# AD.net
KiCad netlist of a schematic drawn in Altium Designer
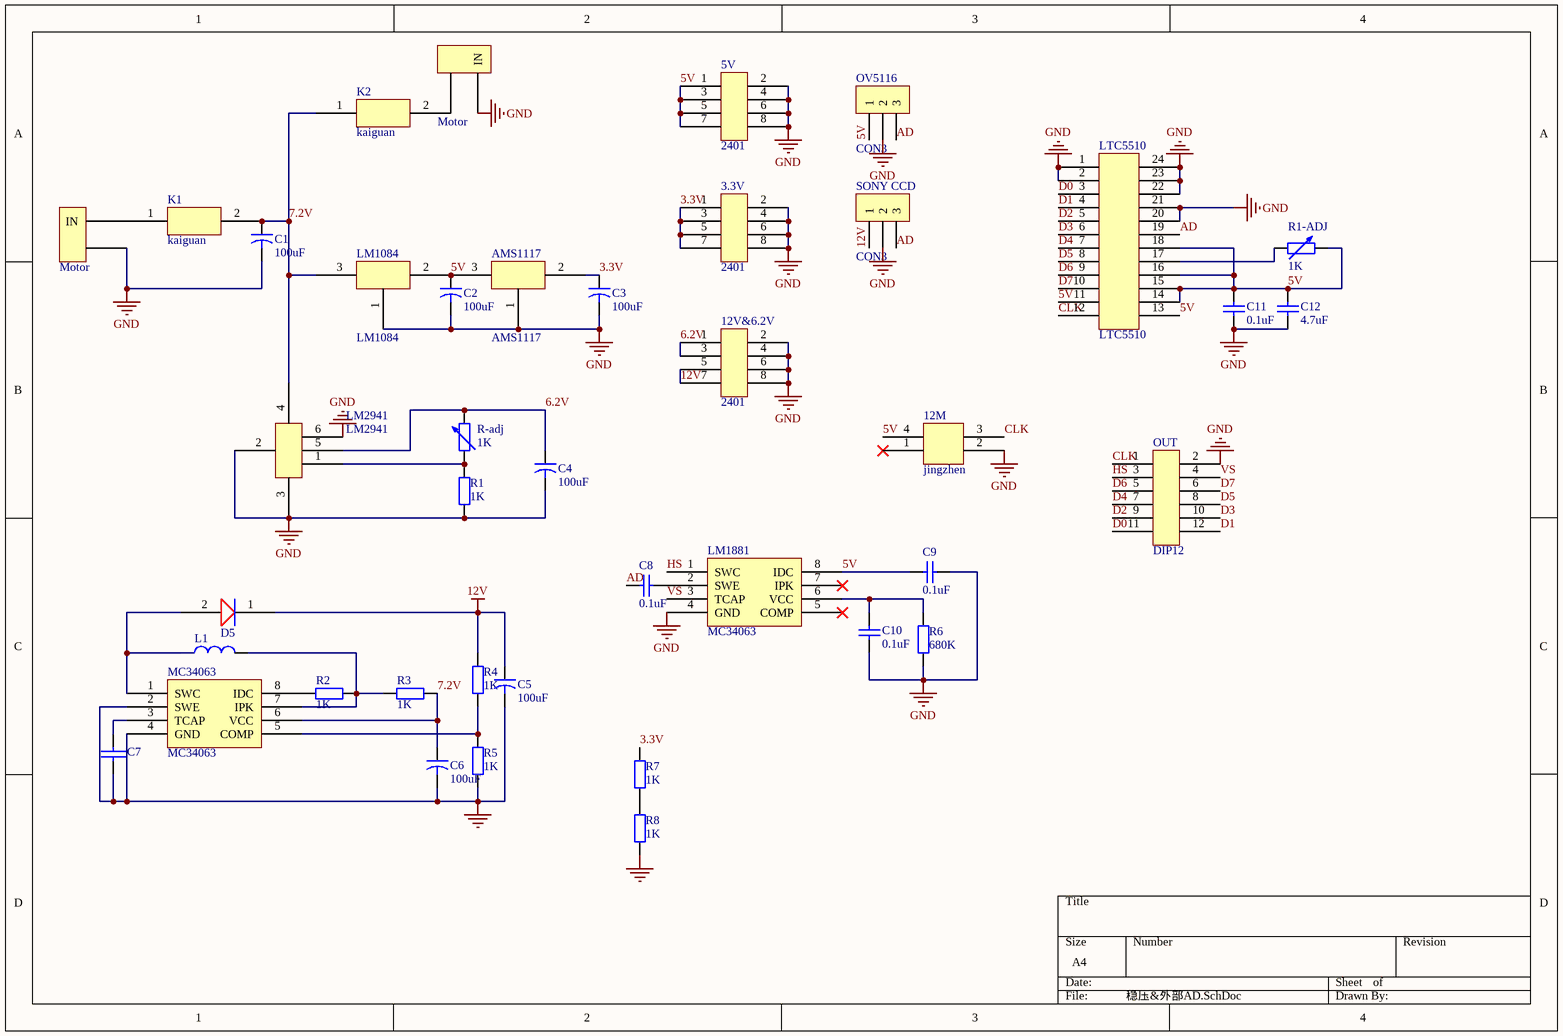
[diagram p0: 稳压&外部AD.SchDoc]

(export (version "E")
  (design (tool "Eeschema 10.0.6"))
  (components
    (comp (ref "3.3V") (value "2401") (footprint "IDC-8") (libsource (lib "Schlib1") (part "2401")))
    (comp (ref "5V") (value "2401") (footprint "IDC-8") (libsource (lib "Schlib1") (part "2401")))
    (comp (ref "12M") (value "jingzhen") (footprint "3225") (libsource (lib "主板常用元器件") (part "jingzhen")))
    (comp (ref "12V&6.2V") (value "2401") (footprint "IDC-8") (libsource (lib "Schlib1") (part "2401")))
    (comp (ref "AMS1117") (value "AMS1117") (footprint "SOT223") (libsource (lib "主板常用元器件") (part "AMS1117")))
    (comp (ref "C1")
      (value "100uF")
      (footprint "CAPPR2-5x6.8")
      (description "Capacitor")
      (fields (field (name "Comment") "Cap2") (field (name "PUBLISHER") "Altium Limited"))
      (libsource (lib "主板常用元器件") (part "Cap2"))
    )
    (comp (ref "C2")
      (value "100uF")
      (footprint "CAPPR2-5x6.8")
      (description "Capacitor")
      (fields (field (name "Comment") "Cap2") (field (name "PUBLISHER") "Altium Limited"))
      (libsource (lib "主板常用元器件") (part "Cap2"))
    )
    (comp (ref "C3")
      (value "100uF")
      (footprint "CAPPR2-5x6.8")
      (description "Capacitor")
      (fields (field (name "Comment") "Cap2") (field (name "PUBLISHER") "Altium Limited"))
      (libsource (lib "主板常用元器件") (part "Cap2"))
    )
    (comp (ref "C4")
      (value "100uF")
      (footprint "CAPPR2-5x6.8")
      (description "Capacitor")
      (fields (field (name "Comment") "Cap2") (field (name "PUBLISHER") "Altium Limited"))
      (libsource (lib "主板常用元器件") (part "Cap2"))
    )
    (comp (ref "C5")
      (value "100uF")
      (footprint "CAPPR2-5x6.8")
      (description "Capacitor")
      (fields (field (name "Comment") "Cap2") (field (name "PUBLISHER") "Altium Limited"))
      (libsource (lib "主板常用元器件") (part "Cap2"))
    )
    (comp (ref "C6")
      (value "100uF")
      (footprint "CAPPR2-5x6.8")
      (description "Capacitor")
      (fields (field (name "Comment") "Cap2") (field (name "PUBLISHER") "Altium Limited"))
      (libsource (lib "主板常用元器件") (part "Cap2"))
    )
    (comp (ref "C7") (value "CAP") (footprint "0805") (libsource (lib "常用元件库") (part "CAP")))
    (comp (ref "C8")
      (value "0.1uF")
      (footprint "0805")
      (description "Capacitor")
      (fields (field (name "Comment") "Cap1") (field (name "PUBLISHER") "Altium Limited"))
      (libsource (lib "主板常用元器件") (part "Cap1"))
    )
    (comp (ref "C9")
      (value "0.1uF")
      (footprint "0805")
      (description "Capacitor")
      (fields (field (name "Comment") "Cap1") (field (name "PUBLISHER") "Altium Limited"))
      (libsource (lib "主板常用元器件") (part "Cap1"))
    )
    (comp (ref "C10")
      (value "0.1uF")
      (footprint "0805")
      (description "Capacitor")
      (fields (field (name "Comment") "Cap1") (field (name "PUBLISHER") "Altium Limited"))
      (libsource (lib "主板常用元器件") (part "Cap1"))
    )
    (comp (ref "C11")
      (value "0.1uF")
      (footprint "0805")
      (description "Capacitor")
      (fields (field (name "Comment") "Cap1") (field (name "PUBLISHER") "Altium Limited"))
      (libsource (lib "主板常用元器件") (part "Cap1"))
    )
    (comp (ref "C12")
      (value "4.7uF")
      (footprint "0805")
      (description "Capacitor")
      (fields (field (name "Comment") "Cap1") (field (name "PUBLISHER") "Altium Limited"))
      (libsource (lib "主板常用元器件") (part "Cap1"))
    )
    (comp (ref "D5") (value "1N5819") (footprint "SMA") (libsource (lib "Schlib1") (part "1N5819")))
    (comp (ref "IN") (value "Motor") (footprint "connection") (libsource (lib "") (part "Motor_1")))
    (comp (ref "K1") (value "kaiguan") (footprint "SIP3") (libsource (lib "主板常用元器件") (part "kaiguan")))
    (comp (ref "K2") (value "kaiguan") (footprint "SIP3") (libsource (lib "主板常用元器件") (part "kaiguan")))
    (comp (ref "L1") (value "L") (footprint "L 5*5mm") (libsource (lib "常用元件库") (part "L")))
    (comp (ref "LM1084") (value "LM1084") (footprint "LM1084") (libsource (lib "主板常用元器件") (part "LM1084")))
    (comp (ref "LM1881") (value "MC34063") (footprint "SO-8") (libsource (lib "Schlib1") (part "MC34063")))
    (comp (ref "LM2941") (value "LM2941") (libsource (lib "主板常用元器件") (part "LM2941")))
    (comp (ref "LTC5510")
      (value "LTC5510")
      (footprint "SOP127P780X200-24N")
      (libsource (lib "主板常用元器件") (part "LTC5510"))
    )
    (comp (ref "MC34063") (value "MC34063") (footprint "SO-8") (libsource (lib "Schlib1") (part "MC34063")))
    (comp (ref "Motor") (value "Motor") (footprint "connection") (libsource (lib "主板常用元器件") (part "Motor")))
    (comp (ref "OUT") (value "DIP12") (footprint "IDC-12") (libsource (lib "主板常用元器件") (part "DIP12")))
    (comp (ref "OV5116") (value "CON3") (footprint "SIP3") (libsource (lib "主板常用元器件") (part "CON3")))
    (comp (ref "R-adj")
      (value "1K")
      (footprint "SIP3")
      (description "Variable Resistor")
      (fields (field (name "Comment") "Res Adj2") (field (name "PUBLISHER") "Altium Limited"))
      (libsource (lib "") (part "Res Adj2_1"))
    )
    (comp (ref "R1")
      (value "1K")
      (footprint "0805")
      (description "Resistor")
      (fields (field (name "Comment") "Res2") (field (name "PUBLISHER") "Altium Limited"))
      (libsource (lib "主板常用元器件") (part "Res2"))
    )
    (comp (ref "R1-ADJ")
      (value "1K")
      (footprint "SIP3")
      (description "Variable Resistor")
      (fields (field (name "Comment") "Res Adj2") (field (name "PUBLISHER") "Altium Limited"))
      (libsource (lib "主板常用元器件") (part "Res Adj2"))
    )
    (comp (ref "R2")
      (value "1K")
      (footprint "0805")
      (description "Resistor")
      (fields (field (name "Comment") "Res2") (field (name "PUBLISHER") "Altium Limited"))
      (libsource (lib "") (part "Res2_1"))
    )
    (comp (ref "R3")
      (value "1K")
      (footprint "0805")
      (description "Resistor")
      (fields (field (name "Comment") "Res2") (field (name "PUBLISHER") "Altium Limited"))
      (libsource (lib "") (part "Res2_1"))
    )
    (comp (ref "R4")
      (value "1K")
      (footprint "0805")
      (description "Resistor")
      (fields (field (name "Comment") "Res2") (field (name "PUBLISHER") "Altium Limited"))
      (libsource (lib "主板常用元器件") (part "Res2"))
    )
    (comp (ref "R5")
      (value "1K")
      (footprint "0805")
      (description "Resistor")
      (fields (field (name "Comment") "Res2") (field (name "PUBLISHER") "Altium Limited"))
      (libsource (lib "主板常用元器件") (part "Res2"))
    )
    (comp (ref "R6")
      (value "680K")
      (footprint "0805")
      (description "Resistor")
      (fields (field (name "Comment") "Res2") (field (name "PUBLISHER") "Altium Limited"))
      (libsource (lib "主板常用元器件") (part "Res2"))
    )
    (comp (ref "R7")
      (value "1K")
      (footprint "0805")
      (description "Resistor")
      (fields (field (name "Comment") "Res2") (field (name "PUBLISHER") "Altium Limited"))
      (libsource (lib "主板常用元器件") (part "Res2"))
    )
    (comp (ref "R8")
      (value "1K")
      (footprint "0805")
      (description "Resistor")
      (fields (field (name "Comment") "Res2") (field (name "PUBLISHER") "Altium Limited"))
      (libsource (lib "主板常用元器件") (part "Res2"))
    )
    (comp (ref "SONY CCD") (value "CON3") (footprint "SIP3") (libsource (lib "主板常用元器件") (part "CON3")))
  )
  (nets
    (net (code "1") (name "/3.3V") (class "Default")
      (node (ref "3.3V") (pin "1") (pinfunction "GND_1") (pintype "passive"))
      (node (ref "3.3V") (pin "3") (pinfunction "CE_3") (pintype "passive"))
      (node (ref "3.3V") (pin "5") (pinfunction "SCK_5") (pintype "passive"))
      (node (ref "3.3V") (pin "7") (pinfunction "MISO_7") (pintype "passive"))
      (node (ref "AMS1117") (pin "2") (pinfunction "OUT_2") (pintype "passive"))
      (node (ref "C3") (pin "1") (pinfunction "1_1") (pintype "passive"))
      (node (ref "R7") (pin "2") (pinfunction "2_2") (pintype "passive"))
    )
    (net (code "2") (name "/5V") (class "Default")
      (node (ref "12M") (pin "4") (pinfunction "VCC_4") (pintype "passive"))
      (node (ref "5V") (pin "1") (pinfunction "GND_1") (pintype "passive"))
      (node (ref "5V") (pin "3") (pinfunction "CE_3") (pintype "passive"))
      (node (ref "5V") (pin "5") (pinfunction "SCK_5") (pintype "passive"))
      (node (ref "5V") (pin "7") (pinfunction "MISO_7") (pintype "passive"))
      (node (ref "AMS1117") (pin "3") (pinfunction "IN_3") (pintype "passive"))
      (node (ref "C11") (pin "2") (pinfunction "2_2") (pintype "passive"))
      (node (ref "C12") (pin "2") (pinfunction "2_2") (pintype "passive"))
      (node (ref "C2") (pin "1") (pinfunction "1_1") (pintype "passive"))
      (node (ref "C9") (pin "1") (pinfunction "1_1") (pintype "passive"))
      (node (ref "LM1084") (pin "2") (pinfunction "OUT_2") (pintype "passive"))
      (node (ref "LM1881") (pin "8") (pinfunction "IDC_8") (pintype "passive"))
      (node (ref "LTC5510") (pin "11") (pinfunction "11_11") (pintype "passive"))
      (node (ref "LTC5510") (pin "13") (pinfunction "13_13") (pintype "passive"))
      (node (ref "LTC5510") (pin "14") (pinfunction "14_14") (pintype "passive"))
      (node (ref "LTC5510") (pin "15") (pinfunction "15_15") (pintype "passive"))
      (node (ref "LTC5510") (pin "16") (pinfunction "16_16") (pintype "passive"))
      (node (ref "LTC5510") (pin "18") (pinfunction "18_18") (pintype "passive"))
      (node (ref "OV5116") (pin "1") (pinfunction "1_1") (pintype "passive"))
      (node (ref "R1-ADJ") (pin "2") (pinfunction "2_2") (pintype "passive"))
    )
    (net (code "3") (name "/6.2V") (class "Default")
      (node (ref "12V&6.2V") (pin "1") (pinfunction "GND_1") (pintype "passive"))
      (node (ref "12V&6.2V") (pin "3") (pinfunction "CE_3") (pintype "passive"))
      (node (ref "C4") (pin "1") (pinfunction "1_1") (pintype "passive"))
      (node (ref "LM2941") (pin "5") (pinfunction "OUT_5") (pintype "passive"))
      (node (ref "R-adj") (pin "2") (pinfunction "2_2") (pintype "passive"))
    )
    (net (code "4") (name "/7.2V") (class "Default")
      (node (ref "C1") (pin "1") (pinfunction "1_1") (pintype "passive"))
      (node (ref "C6") (pin "1") (pinfunction "1_1") (pintype "passive"))
      (node (ref "K1") (pin "2") (pinfunction "IN_2") (pintype "passive"))
      (node (ref "K2") (pin "1") (pinfunction "IN_1") (pintype "passive"))
      (node (ref "LM1084") (pin "3") (pinfunction "IN_3") (pintype "passive"))
      (node (ref "LM2941") (pin "4") (pinfunction "IN_4") (pintype "passive"))
      (node (ref "MC34063") (pin "6") (pinfunction "VCC_6") (pintype "passive"))
      (node (ref "R3") (pin "1") (pinfunction "1_1") (pintype "passive"))
    )
    (net (code "5") (name "/AD") (class "Default")
      (node (ref "C8") (pin "1") (pinfunction "1_1") (pintype "passive"))
      (node (ref "LTC5510") (pin "19") (pinfunction "19_19") (pintype "passive"))
      (node (ref "OV5116") (pin "3") (pinfunction "3_3") (pintype "passive"))
      (node (ref "SONY CCD") (pin "3") (pinfunction "3_3") (pintype "passive"))
    )
    (net (code "6") (name "/CLK") (class "Default")
      (node (ref "12M") (pin "3") (pinfunction "OUT_3") (pintype "passive"))
      (node (ref "LTC5510") (pin "12") (pinfunction "12_12") (pintype "passive"))
      (node (ref "OUT") (pin "1") (pinfunction "1_1") (pintype "passive"))
    )
    (net (code "7") (name "/D0") (class "Default")
      (node (ref "LTC5510") (pin "3") (pinfunction "3_3") (pintype "passive"))
      (node (ref "OUT") (pin "11") (pinfunction "11_11") (pintype "passive"))
    )
    (net (code "8") (name "/D1") (class "Default")
      (node (ref "LTC5510") (pin "4") (pinfunction "4_4") (pintype "passive"))
      (node (ref "OUT") (pin "12") (pinfunction "12_12") (pintype "passive"))
    )
    (net (code "9") (name "/D2") (class "Default")
      (node (ref "LTC5510") (pin "5") (pinfunction "5_5") (pintype "passive"))
      (node (ref "OUT") (pin "9") (pinfunction "9_9") (pintype "passive"))
    )
    (net (code "10") (name "/D3") (class "Default")
      (node (ref "LTC5510") (pin "6") (pinfunction "6_6") (pintype "passive"))
      (node (ref "OUT") (pin "10") (pinfunction "10_10") (pintype "passive"))
    )
    (net (code "11") (name "/D4") (class "Default")
      (node (ref "LTC5510") (pin "7") (pinfunction "7_7") (pintype "passive"))
      (node (ref "OUT") (pin "7") (pinfunction "7_7") (pintype "passive"))
    )
    (net (code "12") (name "/D5") (class "Default")
      (node (ref "LTC5510") (pin "8") (pinfunction "8_8") (pintype "passive"))
      (node (ref "OUT") (pin "8") (pinfunction "8_8") (pintype "passive"))
    )
    (net (code "13") (name "/D6") (class "Default")
      (node (ref "LTC5510") (pin "9") (pinfunction "9_9") (pintype "passive"))
      (node (ref "OUT") (pin "5") (pinfunction "5_5") (pintype "passive"))
    )
    (net (code "14") (name "/D7") (class "Default")
      (node (ref "LTC5510") (pin "10") (pinfunction "10_10") (pintype "passive"))
      (node (ref "OUT") (pin "6") (pinfunction "6_6") (pintype "passive"))
    )
    (net (code "15") (name "/HS") (class "Default")
      (node (ref "LM1881") (pin "1") (pinfunction "SWC_1") (pintype "passive"))
      (node (ref "OUT") (pin "3") (pinfunction "3_3") (pintype "passive"))
    )
    (net (code "16") (name "/VS") (class "Default")
      (node (ref "LM1881") (pin "3") (pinfunction "TCAP_3") (pintype "passive"))
      (node (ref "OUT") (pin "4") (pinfunction "4_4") (pintype "passive"))
    )
    (net (code "17") (name "12V") (class "Default")
      (node (ref "12V&6.2V") (pin "5") (pinfunction "SCK_5") (pintype "passive"))
      (node (ref "12V&6.2V") (pin "7") (pinfunction "MISO_7") (pintype "passive"))
      (node (ref "C5") (pin "1") (pinfunction "1_1") (pintype "passive"))
      (node (ref "D5") (pin "1") (pinfunction "OUT_1") (pintype "passive"))
      (node (ref "R4") (pin "2") (pinfunction "2_2") (pintype "passive"))
      (node (ref "SONY CCD") (pin "1") (pinfunction "1_1") (pintype "passive"))
    )
    (net (code "18") (name "GND") (class "Default")
      (node (ref "12M") (pin "2") (pinfunction "GND_2") (pintype "passive"))
      (node (ref "12V&6.2V") (pin "2") (pinfunction "VCC_2") (pintype "passive"))
      (node (ref "12V&6.2V") (pin "4") (pinfunction "CSN_4") (pintype "passive"))
      (node (ref "12V&6.2V") (pin "6") (pinfunction "MOSI_6") (pintype "passive"))
      (node (ref "12V&6.2V") (pin "8") (pinfunction "IRQ_8") (pintype "passive"))
      (node (ref "3.3V") (pin "2") (pinfunction "VCC_2") (pintype "passive"))
      (node (ref "3.3V") (pin "4") (pinfunction "CSN_4") (pintype "passive"))
      (node (ref "3.3V") (pin "6") (pinfunction "MOSI_6") (pintype "passive"))
      (node (ref "3.3V") (pin "8") (pinfunction "IRQ_8") (pintype "passive"))
      (node (ref "5V") (pin "2") (pinfunction "VCC_2") (pintype "passive"))
      (node (ref "5V") (pin "4") (pinfunction "CSN_4") (pintype "passive"))
      (node (ref "5V") (pin "6") (pinfunction "MOSI_6") (pintype "passive"))
      (node (ref "5V") (pin "8") (pinfunction "IRQ_8") (pintype "passive"))
      (node (ref "AMS1117") (pin "1") (pinfunction "GND_1") (pintype "passive"))
      (node (ref "C1") (pin "2") (pinfunction "2_2") (pintype "passive"))
      (node (ref "C10") (pin "1") (pinfunction "1_1") (pintype "passive"))
      (node (ref "C11") (pin "1") (pinfunction "1_1") (pintype "passive"))
      (node (ref "C12") (pin "1") (pinfunction "1_1") (pintype "passive"))
      (node (ref "C2") (pin "2") (pinfunction "2_2") (pintype "passive"))
      (node (ref "C3") (pin "2") (pinfunction "2_2") (pintype "passive"))
      (node (ref "C4") (pin "2") (pinfunction "2_2") (pintype "passive"))
      (node (ref "C5") (pin "2") (pinfunction "2_2") (pintype "passive"))
      (node (ref "C6") (pin "2") (pinfunction "2_2") (pintype "passive"))
      (node (ref "C7") (pin "2") (pinfunction "2_2") (pintype "passive"))
      (node (ref "C9") (pin "2") (pinfunction "2_2") (pintype "passive"))
      (node (ref "IN") (pin "2") (pinfunction "OUT_2") (pintype "passive"))
      (node (ref "LM1084") (pin "1") (pinfunction "GND_1") (pintype "passive"))
      (node (ref "LM1881") (pin "4") (pinfunction "GND_4") (pintype "passive"))
      (node (ref "LM2941") (pin "2") (pinfunction "OFF_2") (pintype "passive"))
      (node (ref "LM2941") (pin "3") (pinfunction "GND_3") (pintype "passive"))
      (node (ref "LM2941") (pin "6") (pinfunction "OUT_6") (pintype "passive"))
      (node (ref "LTC5510") (pin "1") (pinfunction "1_1") (pintype "passive"))
      (node (ref "LTC5510") (pin "2") (pinfunction "2_2") (pintype "passive"))
      (node (ref "LTC5510") (pin "20") (pinfunction "20_20") (pintype "passive"))
      (node (ref "LTC5510") (pin "21") (pinfunction "21_21") (pintype "passive"))
      (node (ref "LTC5510") (pin "22") (pinfunction "22_22") (pintype "passive"))
      (node (ref "LTC5510") (pin "23") (pinfunction "23_23") (pintype "passive"))
      (node (ref "LTC5510") (pin "24") (pinfunction "24_24") (pintype "passive"))
      (node (ref "MC34063") (pin "2") (pinfunction "SWE_2") (pintype "passive"))
      (node (ref "MC34063") (pin "4") (pinfunction "GND_4") (pintype "passive"))
      (node (ref "Motor") (pin "1") (pinfunction "IN_1") (pintype "passive"))
      (node (ref "OUT") (pin "2") (pinfunction "2_2") (pintype "passive"))
      (node (ref "OV5116") (pin "2") (pinfunction "2_2") (pintype "passive"))
      (node (ref "R1") (pin "1") (pinfunction "1_1") (pintype "passive"))
      (node (ref "R5") (pin "1") (pinfunction "1_1") (pintype "passive"))
      (node (ref "R6") (pin "1") (pinfunction "1_1") (pintype "passive"))
      (node (ref "R8") (pin "1") (pinfunction "1_1") (pintype "passive"))
      (node (ref "SONY CCD") (pin "2") (pinfunction "2_2") (pintype "passive"))
    )
    (net (code "19") (name "Net-(D5-IN)") (class "Default")
      (node (ref "D5") (pin "2") (pinfunction "IN_2") (pintype "passive"))
      (node (ref "L1") (pin "2") (pinfunction "2_2") (pintype "passive"))
      (node (ref "MC34063") (pin "1") (pinfunction "SWC_1") (pintype "passive"))
    )
    (net (code "20") (name "Net-(IN-IN)") (class "Default")
      (node (ref "IN") (pin "1") (pinfunction "IN_1") (pintype "passive"))
      (node (ref "K1") (pin "1") (pinfunction "IN_1") (pintype "passive"))
    )
    (net (code "21") (name "Net-(LM1881-SWE)") (class "Default")
      (node (ref "C8") (pin "2") (pinfunction "2_2") (pintype "passive"))
      (node (ref "LM1881") (pin "2") (pinfunction "SWE_2") (pintype "passive"))
    )
    (net (code "22") (name "Net-(LM1881-VCC)") (class "Default")
      (node (ref "C10") (pin "2") (pinfunction "2_2") (pintype "passive"))
      (node (ref "LM1881") (pin "6") (pinfunction "VCC_6") (pintype "passive"))
      (node (ref "R6") (pin "2") (pinfunction "2_2") (pintype "passive"))
    )
    (net (code "23") (name "Net-(LM2941-ADJ)") (class "Default")
      (node (ref "LM2941") (pin "1") (pinfunction "ADJ_1") (pintype "passive"))
      (node (ref "R-adj") (pin "1") (pinfunction "1_1") (pintype "passive"))
      (node (ref "R1") (pin "2") (pinfunction "2_2") (pintype "passive"))
    )
    (net (code "24") (name "Net-(LTC5510-Pad17)") (class "Default")
      (node (ref "LTC5510") (pin "17") (pinfunction "17_17") (pintype "passive"))
      (node (ref "R1-ADJ") (pin "1") (pinfunction "1_1") (pintype "passive"))
    )
    (net (code "25") (name "Net-(MC34063-COMP)") (class "Default")
      (node (ref "MC34063") (pin "5") (pinfunction "COMP_5") (pintype "passive"))
      (node (ref "R4") (pin "1") (pinfunction "1_1") (pintype "passive"))
      (node (ref "R5") (pin "2") (pinfunction "2_2") (pintype "passive"))
    )
    (net (code "26") (name "Net-(MC34063-IDC)") (class "Default")
      (node (ref "MC34063") (pin "8") (pinfunction "IDC_8") (pintype "passive"))
      (node (ref "R2") (pin "2") (pinfunction "2_2") (pintype "passive"))
    )
    (net (code "27") (name "Net-(MC34063-IPK)") (class "Default")
      (node (ref "L1") (pin "1") (pinfunction "1_1") (pintype "passive"))
      (node (ref "MC34063") (pin "7") (pinfunction "IPK_7") (pintype "passive"))
      (node (ref "R2") (pin "1") (pinfunction "1_1") (pintype "passive"))
      (node (ref "R3") (pin "2") (pinfunction "2_2") (pintype "passive"))
    )
    (net (code "28") (name "Net-(MC34063-TCAP)") (class "Default")
      (node (ref "C7") (pin "1") (pinfunction "1_1") (pintype "passive"))
      (node (ref "MC34063") (pin "3") (pinfunction "TCAP_3") (pintype "passive"))
    )
    (net (code "29") (name "Net-(Motor-OUT)") (class "Default")
      (node (ref "K2") (pin "2") (pinfunction "IN_2") (pintype "passive"))
      (node (ref "Motor") (pin "2") (pinfunction "OUT_2") (pintype "passive"))
    )
    (net (code "30") (name "Net-(R7-Pad1)") (class "Default")
      (node (ref "R7") (pin "1") (pinfunction "1_1") (pintype "passive"))
      (node (ref "R8") (pin "2") (pinfunction "2_2") (pintype "passive"))
    )
    (net (code "31") (name "unconnected-(12M-NC-Pad1)") (class "Default")
      (node (ref "12M") (pin "1") (pinfunction "NC_1") (pintype "passive+no_connect"))
    )
    (net (code "32") (name "unconnected-(LM1881-COMP-Pad5)") (class "Default")
      (node (ref "LM1881") (pin "5") (pinfunction "COMP_5") (pintype "passive+no_connect"))
    )
    (net (code "33") (name "unconnected-(LM1881-IPK-Pad7)") (class "Default")
      (node (ref "LM1881") (pin "7") (pinfunction "IPK_7") (pintype "passive+no_connect"))
    )
  )
)
